# Wiiext-NES_Mini-SNES_Mini.net
KiCad netlist of a schematic drawn in EAGLE
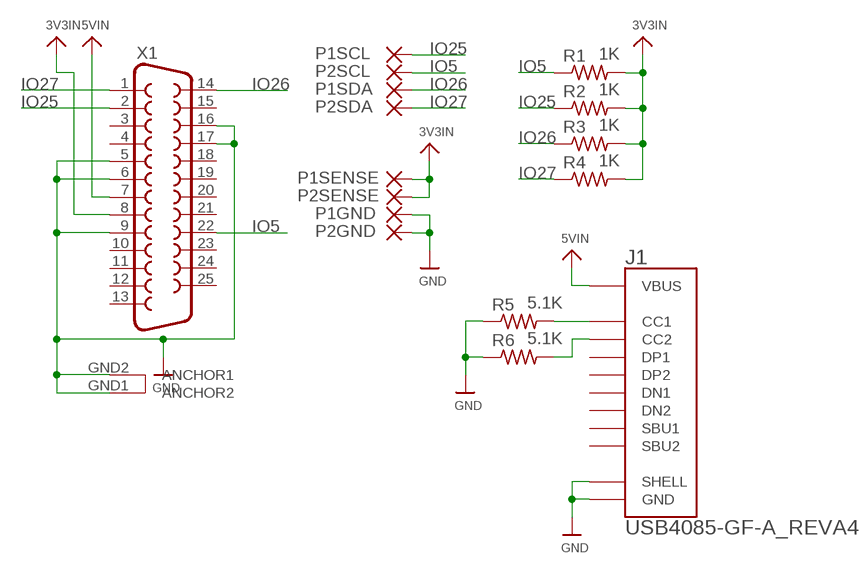
[diagram p0: schematic, sheet 1]

(export (version "E")
  (design (tool "Eeschema 10.0.6"))
  (components
    (comp (ref "J1")
      (value "USB4085-GF-A_REVA4")
      (footprint "eagle-import:GCT_USB4085-GF-A_REVA4")
      (fields
        (field (name "DIGI-KEY_PART_NUMBER") "2073-USB4085-GF-ATR-ND")
        (field (name "MF") "Global Connector Technology")
        (field (name "MP") "USB4085-GF-A")
      )
      (libsource (lib "eagle-import") (part "USB4085-GF-A_REVA4"))
    )
    (comp (ref "P1GND")
      (value "SMD5")
      (footprint "eagle-import:SMD2,54-5,08")
      (libsource (lib "eagle-import") (part "SMD5"))
    )
    (comp (ref "P1SCL")
      (value "SMD5")
      (footprint "eagle-import:SMD2,54-5,08")
      (libsource (lib "eagle-import") (part "SMD5"))
    )
    (comp (ref "P1SDA")
      (value "SMD5")
      (footprint "eagle-import:SMD2,54-5,08")
      (libsource (lib "eagle-import") (part "SMD5"))
    )
    (comp (ref "P1SENSE")
      (value "SMD5")
      (footprint "eagle-import:SMD2,54-5,08")
      (libsource (lib "eagle-import") (part "SMD5"))
    )
    (comp (ref "P2GND")
      (value "SMD5")
      (footprint "eagle-import:SMD2,54-5,08")
      (libsource (lib "eagle-import") (part "SMD5"))
    )
    (comp (ref "P2SCL")
      (value "SMD5")
      (footprint "eagle-import:SMD2,54-5,08")
      (libsource (lib "eagle-import") (part "SMD5"))
    )
    (comp (ref "P2SDA")
      (value "SMD5")
      (footprint "eagle-import:SMD2,54-5,08")
      (libsource (lib "eagle-import") (part "SMD5"))
    )
    (comp (ref "P2SENSE")
      (value "SMD5")
      (footprint "eagle-import:SMD2,54-5,08")
      (libsource (lib "eagle-import") (part "SMD5"))
    )
    (comp (ref "R1")
      (value "1K")
      (footprint "eagle-import:R1206")
      (libsource (lib "eagle-import") (part "R-US_R1206"))
    )
    (comp (ref "R2")
      (value "1K")
      (footprint "eagle-import:R1206")
      (libsource (lib "eagle-import") (part "R-US_R1206"))
    )
    (comp (ref "R3")
      (value "1K")
      (footprint "eagle-import:R1206")
      (libsource (lib "eagle-import") (part "R-US_R1206"))
    )
    (comp (ref "R4")
      (value "1K")
      (footprint "eagle-import:R1206")
      (libsource (lib "eagle-import") (part "R-US_R1206"))
    )
    (comp (ref "R5")
      (value "5.1K")
      (footprint "eagle-import:R1206")
      (libsource (lib "eagle-import") (part "R-US_R1206"))
    )
    (comp (ref "R6")
      (value "5.1K")
      (footprint "eagle-import:R1206")
      (libsource (lib "eagle-import") (part "R-US_R1206"))
    )
    (comp (ref "X1")
      (value "DB25_FEMALEHP")
      (footprint "eagle-import:F25HP")
      (libsource (lib "eagle-import") (part "DB25_FEMALEHP"))
    )
  )
  (nets
    (net (code "1") (name "/IO5") (class "Default")
      (node (ref "P2SCL") (pin "1") (pinfunction "P_1") (pintype "passive"))
      (node (ref "R1") (pin "1") (pinfunction "1_1") (pintype "passive"))
      (node (ref "X1") (pin "22") (pinfunction "22_22") (pintype "passive"))
    )
    (net (code "2") (name "/IO25") (class "Default")
      (node (ref "P1SCL") (pin "1") (pinfunction "P_1") (pintype "passive"))
      (node (ref "R2") (pin "1") (pinfunction "1_1") (pintype "passive"))
      (node (ref "X1") (pin "2") (pinfunction "2_2") (pintype "passive"))
    )
    (net (code "3") (name "/IO26") (class "Default")
      (node (ref "P1SDA") (pin "1") (pinfunction "P_1") (pintype "passive"))
      (node (ref "R3") (pin "1") (pinfunction "1_1") (pintype "passive"))
      (node (ref "X1") (pin "14") (pinfunction "14_14") (pintype "passive"))
    )
    (net (code "4") (name "/IO27") (class "Default")
      (node (ref "P2SDA") (pin "1") (pinfunction "P_1") (pintype "passive"))
      (node (ref "R4") (pin "1") (pinfunction "1_1") (pintype "passive"))
      (node (ref "X1") (pin "1") (pinfunction "1_1") (pintype "passive"))
    )
    (net (code "5") (name "3V3IN") (class "Default")
      (node (ref "P1SENSE") (pin "1") (pinfunction "P_1") (pintype "passive"))
      (node (ref "P2SENSE") (pin "1") (pinfunction "P_1") (pintype "passive"))
      (node (ref "R1") (pin "2") (pinfunction "2_2") (pintype "passive"))
      (node (ref "R2") (pin "2") (pinfunction "2_2") (pintype "passive"))
      (node (ref "R3") (pin "2") (pinfunction "2_2") (pintype "passive"))
      (node (ref "R4") (pin "2") (pinfunction "2_2") (pintype "passive"))
      (node (ref "X1") (pin "8") (pinfunction "8_8") (pintype "passive"))
    )
    (net (code "6") (name "5VIN") (class "Default")
      (node (ref "J1") (pin "A4") (pinfunction "VBUS_A4") (pintype "power_in"))
      (node (ref "J1") (pin "A9") (pinfunction "VBUS_A9") (pintype "power_in"))
      (node (ref "J1") (pin "B4") (pinfunction "VBUS_B4") (pintype "power_in"))
      (node (ref "J1") (pin "B9") (pinfunction "VBUS_B9") (pintype "power_in"))
      (node (ref "X1") (pin "7") (pinfunction "7_7") (pintype "passive"))
    )
    (net (code "7") (name "GND") (class "Default")
      (node (ref "J1") (pin "A1") (pinfunction "GND_A1") (pintype "power_in"))
      (node (ref "J1") (pin "A12") (pinfunction "GND_A12") (pintype "power_in"))
      (node (ref "J1") (pin "B1") (pinfunction "GND_B1") (pintype "power_in"))
      (node (ref "J1") (pin "B12") (pinfunction "GND_B12") (pintype "power_in"))
      (node (ref "J1") (pin "S1") (pinfunction "SHELL_S1") (pintype "passive"))
      (node (ref "J1") (pin "S2") (pinfunction "SHELL_S2") (pintype "passive"))
      (node (ref "J1") (pin "S3") (pinfunction "SHELL_S3") (pintype "passive"))
      (node (ref "J1") (pin "S4") (pinfunction "SHELL_S4") (pintype "passive"))
      (node (ref "P1GND") (pin "1") (pinfunction "P_1") (pintype "passive"))
      (node (ref "P2GND") (pin "1") (pinfunction "P_1") (pintype "passive"))
      (node (ref "R5") (pin "1") (pinfunction "1_1") (pintype "passive"))
      (node (ref "R6") (pin "1") (pinfunction "1_1") (pintype "passive"))
      (node (ref "X1") (pin "16") (pinfunction "16_16") (pintype "passive"))
      (node (ref "X1") (pin "17") (pinfunction "17_17") (pintype "passive"))
      (node (ref "X1") (pin "5") (pinfunction "5_5") (pintype "passive"))
      (node (ref "X1") (pin "6") (pinfunction "6_6") (pintype "passive"))
      (node (ref "X1") (pin "9") (pinfunction "9_9") (pintype "passive"))
      (node (ref "X1") (pin "GND1") (pinfunction "ANCHOR2_GND1") (pintype "bidirectional"))
      (node (ref "X1") (pin "GND2") (pinfunction "ANCHOR1_GND2") (pintype "bidirectional"))
    )
    (net (code "8") (name "Net-(J1-CC1)") (class "Default")
      (node (ref "J1") (pin "A5") (pinfunction "CC1_A5") (pintype "bidirectional"))
      (node (ref "R5") (pin "2") (pinfunction "2_2") (pintype "passive"))
    )
    (net (code "9") (name "Net-(J1-CC2)") (class "Default")
      (node (ref "J1") (pin "B5") (pinfunction "CC2_B5") (pintype "bidirectional"))
      (node (ref "R6") (pin "2") (pinfunction "2_2") (pintype "passive"))
    )
    (net (code "10") (name "unconnected-(J1-DN1-PadA7)") (class "Default")
      (node (ref "J1") (pin "A7") (pinfunction "DN1_A7") (pintype "bidirectional"))
    )
    (net (code "11") (name "unconnected-(J1-DN2-PadB7)") (class "Default")
      (node (ref "J1") (pin "B7") (pinfunction "DN2_B7") (pintype "bidirectional"))
    )
    (net (code "12") (name "unconnected-(J1-DP1-PadA6)") (class "Default")
      (node (ref "J1") (pin "A6") (pinfunction "DP1_A6") (pintype "bidirectional"))
    )
    (net (code "13") (name "unconnected-(J1-DP2-PadB6)") (class "Default")
      (node (ref "J1") (pin "B6") (pinfunction "DP2_B6") (pintype "bidirectional"))
    )
    (net (code "14") (name "unconnected-(J1-SBU1-PadA8)") (class "Default")
      (node (ref "J1") (pin "A8") (pinfunction "SBU1_A8") (pintype "bidirectional"))
    )
    (net (code "15") (name "unconnected-(J1-SBU2-PadB8)") (class "Default")
      (node (ref "J1") (pin "B8") (pinfunction "SBU2_B8") (pintype "bidirectional"))
    )
    (net (code "16") (name "unconnected-(X1-Pad3)") (class "Default")
      (node (ref "X1") (pin "3") (pinfunction "3_3") (pintype "passive"))
    )
    (net (code "17") (name "unconnected-(X1-Pad4)") (class "Default")
      (node (ref "X1") (pin "4") (pinfunction "4_4") (pintype "passive"))
    )
    (net (code "18") (name "unconnected-(X1-Pad10)") (class "Default")
      (node (ref "X1") (pin "10") (pinfunction "10_10") (pintype "passive"))
    )
    (net (code "19") (name "unconnected-(X1-Pad11)") (class "Default")
      (node (ref "X1") (pin "11") (pinfunction "11_11") (pintype "passive"))
    )
    (net (code "20") (name "unconnected-(X1-Pad12)") (class "Default")
      (node (ref "X1") (pin "12") (pinfunction "12_12") (pintype "passive"))
    )
    (net (code "21") (name "unconnected-(X1-Pad13)") (class "Default")
      (node (ref "X1") (pin "13") (pinfunction "13_13") (pintype "passive"))
    )
    (net (code "22") (name "unconnected-(X1-Pad15)") (class "Default")
      (node (ref "X1") (pin "15") (pinfunction "15_15") (pintype "passive"))
    )
    (net (code "23") (name "unconnected-(X1-Pad18)") (class "Default")
      (node (ref "X1") (pin "18") (pinfunction "18_18") (pintype "passive"))
    )
    (net (code "24") (name "unconnected-(X1-Pad19)") (class "Default")
      (node (ref "X1") (pin "19") (pinfunction "19_19") (pintype "passive"))
    )
    (net (code "25") (name "unconnected-(X1-Pad20)") (class "Default")
      (node (ref "X1") (pin "20") (pinfunction "20_20") (pintype "passive"))
    )
    (net (code "26") (name "unconnected-(X1-Pad21)") (class "Default")
      (node (ref "X1") (pin "21") (pinfunction "21_21") (pintype "passive"))
    )
    (net (code "27") (name "unconnected-(X1-Pad23)") (class "Default")
      (node (ref "X1") (pin "23") (pinfunction "23_23") (pintype "passive"))
    )
    (net (code "28") (name "unconnected-(X1-Pad24)") (class "Default")
      (node (ref "X1") (pin "24") (pinfunction "24_24") (pintype "passive"))
    )
    (net (code "29") (name "unconnected-(X1-Pad25)") (class "Default")
      (node (ref "X1") (pin "25") (pinfunction "25_25") (pintype "passive"))
    )
  )
)
